# 1_P2_schdoc.net
KiCad netlist of a schematic drawn in Altium Designer
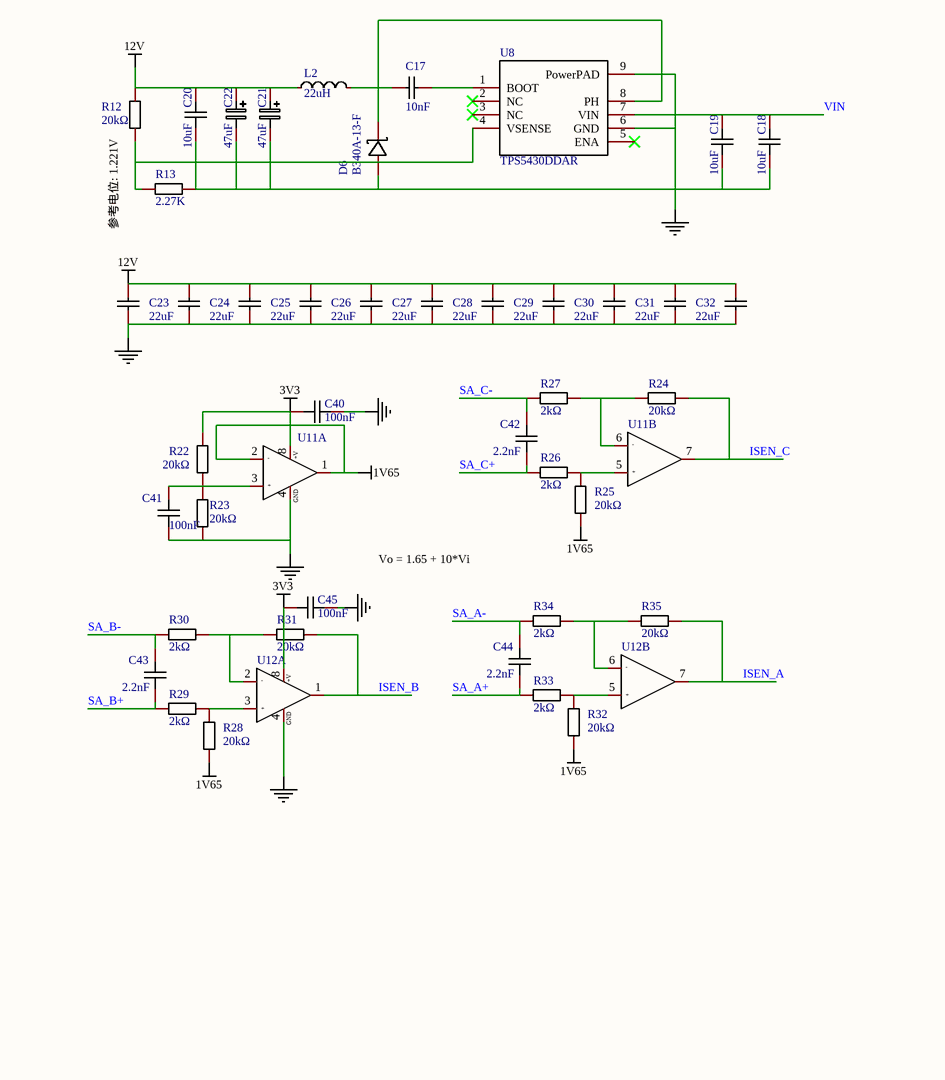
[diagram p0: 1_P2.schdoc.schdoc]

(export (version "E")
  (design (tool "Eeschema 10.0.6"))
  (components
    (comp (ref "C17")
      (value "10nF")
      (fields
        (field (name "NAME") "10nF")
        (field (name "MANUFACTURER") "YAGEO(国巨)")
        (field (name "MANUFACTURER PART") "CC0603KRX7R9BB103")
        (field (name "TOLERANCE") "±10%")
      )
      (libsource (lib "altium-import") (part "root_0_CC0603KRX7R9BB103_"))
    )
    (comp (ref "C18")
      (value "10uF")
      (fields
        (field (name "NAME") "10uF")
        (field (name "MANUFACTURER") "muRata(村田)")
        (field (name "MANUFACTURER PART") "GRM21BR61H106KE43L")
        (field (name "TOLERANCE") "±10%")
      )
      (libsource (lib "altium-import") (part "root_1_GRM21BR61H106KE43L_"))
    )
    (comp (ref "C19")
      (value "10uF")
      (fields
        (field (name "NAME") "10uF")
        (field (name "MANUFACTURER") "muRata(村田)")
        (field (name "MANUFACTURER PART") "GRM21BR61H106KE43L")
        (field (name "TOLERANCE") "±10%")
      )
      (libsource (lib "altium-import") (part "root_1_GRM21BR61H106KE43L_"))
    )
    (comp (ref "C20")
      (value "10uF")
      (fields
        (field (name "NAME") "10uF")
        (field (name "MANUFACTURER") "muRata(村田)")
        (field (name "MANUFACTURER PART") "GRM21BR61H106KE43L")
        (field (name "TOLERANCE") "±10%")
      )
      (libsource (lib "altium-import") (part "root_1_GRM21BR61H106KE43L_"))
    )
    (comp (ref "C21")
      (value "47uF")
      (fields
        (field (name "NAME") "47uF")
        (field (name "MANUFACTURER") "CEC(振华新云)")
        (field (name "MANUFACTURER PART") "CA45-B-16V-47uF-K")
        (field (name "TOLERANCE") "±10%")
      )
      (libsource (lib "altium-import") (part "root_1_CA45-B-16V-47uF-K_"))
    )
    (comp (ref "C22")
      (value "47uF")
      (fields
        (field (name "NAME") "47uF")
        (field (name "MANUFACTURER") "CEC(振华新云)")
        (field (name "MANUFACTURER PART") "CA45-B-16V-47uF-K")
        (field (name "TOLERANCE") "±10%")
      )
      (libsource (lib "altium-import") (part "root_1_CA45-B-16V-47uF-K_"))
    )
    (comp (ref "C23")
      (value "22uF")
      (fields
        (field (name "NAME") "22uF")
        (field (name "MANUFACTURER PART") "CL31A226KAHNNNE")
        (field (name "MANUFACTURER") "SAMSUNG(三星)")
        (field (name "TOLERANCE") "±10%")
      )
      (libsource (lib "altium-import") (part "root_1_CL31A226KAHNNNE_"))
    )
    (comp (ref "C24")
      (value "22uF")
      (fields
        (field (name "NAME") "22uF")
        (field (name "MANUFACTURER PART") "CL31A226KAHNNNE")
        (field (name "MANUFACTURER") "SAMSUNG(三星)")
        (field (name "TOLERANCE") "±10%")
      )
      (libsource (lib "altium-import") (part "root_1_CL31A226KAHNNNE_"))
    )
    (comp (ref "C25")
      (value "22uF")
      (fields
        (field (name "NAME") "22uF")
        (field (name "MANUFACTURER PART") "CL31A226KAHNNNE")
        (field (name "MANUFACTURER") "SAMSUNG(三星)")
        (field (name "TOLERANCE") "±10%")
      )
      (libsource (lib "altium-import") (part "root_1_CL31A226KAHNNNE_"))
    )
    (comp (ref "C26")
      (value "22uF")
      (fields
        (field (name "NAME") "22uF")
        (field (name "MANUFACTURER PART") "CL31A226KAHNNNE")
        (field (name "MANUFACTURER") "SAMSUNG(三星)")
        (field (name "TOLERANCE") "±10%")
      )
      (libsource (lib "altium-import") (part "root_1_CL31A226KAHNNNE_"))
    )
    (comp (ref "C27")
      (value "22uF")
      (fields
        (field (name "NAME") "22uF")
        (field (name "MANUFACTURER PART") "CL31A226KAHNNNE")
        (field (name "MANUFACTURER") "SAMSUNG(三星)")
        (field (name "TOLERANCE") "±10%")
      )
      (libsource (lib "altium-import") (part "root_1_CL31A226KAHNNNE_"))
    )
    (comp (ref "C28")
      (value "22uF")
      (fields
        (field (name "NAME") "22uF")
        (field (name "MANUFACTURER PART") "CL31A226KAHNNNE")
        (field (name "MANUFACTURER") "SAMSUNG(三星)")
        (field (name "TOLERANCE") "±10%")
      )
      (libsource (lib "altium-import") (part "root_1_CL31A226KAHNNNE_"))
    )
    (comp (ref "C29")
      (value "22uF")
      (fields
        (field (name "NAME") "22uF")
        (field (name "MANUFACTURER PART") "CL31A226KAHNNNE")
        (field (name "MANUFACTURER") "SAMSUNG(三星)")
        (field (name "TOLERANCE") "±10%")
      )
      (libsource (lib "altium-import") (part "root_1_CL31A226KAHNNNE_"))
    )
    (comp (ref "C30")
      (value "22uF")
      (fields
        (field (name "NAME") "22uF")
        (field (name "MANUFACTURER PART") "CL31A226KAHNNNE")
        (field (name "MANUFACTURER") "SAMSUNG(三星)")
        (field (name "TOLERANCE") "±10%")
      )
      (libsource (lib "altium-import") (part "root_1_CL31A226KAHNNNE_"))
    )
    (comp (ref "C31")
      (value "22uF")
      (fields
        (field (name "NAME") "22uF")
        (field (name "MANUFACTURER PART") "CL31A226KAHNNNE")
        (field (name "MANUFACTURER") "SAMSUNG(三星)")
        (field (name "TOLERANCE") "±10%")
      )
      (libsource (lib "altium-import") (part "root_1_CL31A226KAHNNNE_"))
    )
    (comp (ref "C32")
      (value "22uF")
      (fields
        (field (name "NAME") "22uF")
        (field (name "MANUFACTURER PART") "CL31A226KAHNNNE")
        (field (name "MANUFACTURER") "SAMSUNG(三星)")
        (field (name "TOLERANCE") "±10%")
      )
      (libsource (lib "altium-import") (part "root_1_CL31A226KAHNNNE_"))
    )
    (comp (ref "C33")
      (value "22uF")
      (fields
        (field (name "MANUFACTURER PART") "CL31A226KAHNNNE")
        (field (name "MANUFACTURER") "SAMSUNG(三星)")
        (field (name "TOLERANCE") "±10%")
      )
      (libsource (lib "altium-import") (part "root_1_CL31A226KAHNNNE_"))
    )
    (comp (ref "C40")
      (value "100nF")
      (fields
        (field (name "NAME") "100nF")
        (field (name "MANUFACTURER") "FH(风华)")
        (field (name "MANUFACTURER PART") "0603B104K500NT")
        (field (name "TOLERANCE") "±10%")
      )
      (libsource (lib "altium-import") (part "root_0_0603B104K500NT_"))
    )
    (comp (ref "C41")
      (value "100nF")
      (fields
        (field (name "NAME") "100nF")
        (field (name "MANUFACTURER") "FH(风华)")
        (field (name "MANUFACTURER PART") "0603B104K500NT")
        (field (name "TOLERANCE") "±10%")
      )
      (libsource (lib "altium-import") (part "root_1_0603B104K500NT_"))
    )
    (comp (ref "C42")
      (value "2.2nF")
      (fields
        (field (name "NAME") "2.2nF")
        (field (name "MANUFACTURER") "FH(风华)")
        (field (name "MANUFACTURER PART") "0603B222K500NT")
        (field (name "TOLERANCE") "±10%")
      )
      (libsource (lib "altium-import") (part "root_1_0603B222K500NT_"))
    )
    (comp (ref "C43")
      (value "2.2nF")
      (fields
        (field (name "NAME") "2.2nF")
        (field (name "MANUFACTURER") "FH(风华)")
        (field (name "MANUFACTURER PART") "0603B222K500NT")
        (field (name "TOLERANCE") "±10%")
      )
      (libsource (lib "altium-import") (part "root_1_0603B222K500NT_"))
    )
    (comp (ref "C44")
      (value "2.2nF")
      (fields
        (field (name "NAME") "2.2nF")
        (field (name "MANUFACTURER") "FH(风华)")
        (field (name "MANUFACTURER PART") "0603B222K500NT")
        (field (name "TOLERANCE") "±10%")
      )
      (libsource (lib "altium-import") (part "root_1_0603B222K500NT_"))
    )
    (comp (ref "C45")
      (value "100nF")
      (fields
        (field (name "NAME") "100nF")
        (field (name "MANUFACTURER") "FH(风华)")
        (field (name "MANUFACTURER PART") "0603B104K500NT")
        (field (name "TOLERANCE") "±10%")
      )
      (libsource (lib "altium-import") (part "root_0_0603B104K500NT_"))
    )
    (comp (ref "D6")
      (value "B340A-13-F")
      (description "正向压降(Vf):500mV@3A;直流反向耐压(Vr):40V;平均整流电流(Io):3A;")
      (fields (field (name "NAME") "B340A-13-F") (field (name "MANUFACTURER") "DIODES(美台)"))
      (libsource (lib "altium-import") (part "root_3_B340A-13-F_"))
    )
    (comp (ref "L2")
      (value "22uH")
      (fields
        (field (name "NAME") "22uH")
        (field (name "MANUFACTURER") "cjiang(长江微电)")
        (field (name "MANUFACTURER PART") "FXL0630-220-M")
        (field (name "TOLERANCE") "±20%")
      )
      (libsource (lib "altium-import") (part "root_0_FXL0630-220-M_"))
    )
    (comp (ref "R12")
      (value "20kΩ")
      (fields
        (field (name "NAME") "20kΩ")
        (field (name "MANUFACTURER") "UNI-ROYAL(厚声)")
        (field (name "MANUFACTURER PART") "0603WAF2002T5E")
        (field (name "TOLERANCE") "±1%")
      )
      (libsource (lib "altium-import") (part "root_1_0603WAF2002T5E_"))
    )
    (comp (ref "R13")
      (value "2.27K")
      (fields (field (name "NAME") "2.27K"))
      (libsource (lib "altium-import") (part "root_2_Res_0603_"))
    )
    (comp (ref "R22")
      (value "20kΩ")
      (fields
        (field (name "NAME") "20kΩ")
        (field (name "MANUFACTURER") "UNI-ROYAL(厚声)")
        (field (name "MANUFACTURER PART") "0603WAF2002T5E")
        (field (name "TOLERANCE") "±1%")
      )
      (libsource (lib "altium-import") (part "root_1_0603WAF2002T5E_"))
    )
    (comp (ref "R23")
      (value "20kΩ")
      (fields
        (field (name "NAME") "20kΩ")
        (field (name "MANUFACTURER") "UNI-ROYAL(厚声)")
        (field (name "MANUFACTURER PART") "0603WAF2002T5E")
        (field (name "TOLERANCE") "±1%")
      )
      (libsource (lib "altium-import") (part "root_1_0603WAF2002T5E_"))
    )
    (comp (ref "R24")
      (value "20kΩ")
      (fields
        (field (name "NAME") "20kΩ")
        (field (name "MANUFACTURER") "UNI-ROYAL(厚声)")
        (field (name "MANUFACTURER PART") "0603WAF2002T5E")
        (field (name "TOLERANCE") "±1%")
      )
      (libsource (lib "altium-import") (part "root_0_0603WAF2002T5E_"))
    )
    (comp (ref "R25")
      (value "20kΩ")
      (fields
        (field (name "NAME") "20kΩ")
        (field (name "MANUFACTURER") "UNI-ROYAL(厚声)")
        (field (name "MANUFACTURER PART") "0603WAF2002T5E")
        (field (name "TOLERANCE") "±1%")
      )
      (libsource (lib "altium-import") (part "root_1_0603WAF2002T5E_"))
    )
    (comp (ref "R26")
      (value "2kΩ")
      (fields
        (field (name "NAME") "2kΩ")
        (field (name "MANUFACTURER") "UNI-ROYAL(厚声)")
        (field (name "MANUFACTURER PART") "0603WAF2001T5E")
        (field (name "TOLERANCE") "±1%")
      )
      (libsource (lib "altium-import") (part "root_0_0603WAF2001T5E_"))
    )
    (comp (ref "R27")
      (value "2kΩ")
      (fields
        (field (name "NAME") "2kΩ")
        (field (name "MANUFACTURER") "UNI-ROYAL(厚声)")
        (field (name "MANUFACTURER PART") "0603WAF2001T5E")
        (field (name "TOLERANCE") "±1%")
      )
      (libsource (lib "altium-import") (part "root_0_0603WAF2001T5E_"))
    )
    (comp (ref "R28")
      (value "20kΩ")
      (fields
        (field (name "NAME") "20kΩ")
        (field (name "MANUFACTURER") "UNI-ROYAL(厚声)")
        (field (name "MANUFACTURER PART") "0603WAF2002T5E")
        (field (name "TOLERANCE") "±1%")
      )
      (libsource (lib "altium-import") (part "root_1_0603WAF2002T5E_"))
    )
    (comp (ref "R29")
      (value "2kΩ")
      (fields
        (field (name "NAME") "2kΩ")
        (field (name "MANUFACTURER") "UNI-ROYAL(厚声)")
        (field (name "MANUFACTURER PART") "0603WAF2001T5E")
        (field (name "TOLERANCE") "±1%")
      )
      (libsource (lib "altium-import") (part "root_0_0603WAF2001T5E_"))
    )
    (comp (ref "R30")
      (value "2kΩ")
      (fields
        (field (name "NAME") "2kΩ")
        (field (name "MANUFACTURER") "UNI-ROYAL(厚声)")
        (field (name "MANUFACTURER PART") "0603WAF2001T5E")
        (field (name "TOLERANCE") "±1%")
      )
      (libsource (lib "altium-import") (part "root_0_0603WAF2001T5E_"))
    )
    (comp (ref "R31")
      (value "20kΩ")
      (fields
        (field (name "NAME") "20kΩ")
        (field (name "MANUFACTURER") "UNI-ROYAL(厚声)")
        (field (name "MANUFACTURER PART") "0603WAF2002T5E")
        (field (name "TOLERANCE") "±1%")
      )
      (libsource (lib "altium-import") (part "root_0_0603WAF2002T5E_"))
    )
    (comp (ref "R32")
      (value "20kΩ")
      (fields
        (field (name "NAME") "20kΩ")
        (field (name "MANUFACTURER") "UNI-ROYAL(厚声)")
        (field (name "MANUFACTURER PART") "0603WAF2002T5E")
        (field (name "TOLERANCE") "±1%")
      )
      (libsource (lib "altium-import") (part "root_1_0603WAF2002T5E_"))
    )
    (comp (ref "R33")
      (value "2kΩ")
      (fields
        (field (name "NAME") "2kΩ")
        (field (name "MANUFACTURER") "UNI-ROYAL(厚声)")
        (field (name "MANUFACTURER PART") "0603WAF2001T5E")
        (field (name "TOLERANCE") "±1%")
      )
      (libsource (lib "altium-import") (part "root_0_0603WAF2001T5E_"))
    )
    (comp (ref "R34")
      (value "2kΩ")
      (fields
        (field (name "NAME") "2kΩ")
        (field (name "MANUFACTURER") "UNI-ROYAL(厚声)")
        (field (name "MANUFACTURER PART") "0603WAF2001T5E")
        (field (name "TOLERANCE") "±1%")
      )
      (libsource (lib "altium-import") (part "root_0_0603WAF2001T5E_"))
    )
    (comp (ref "R35")
      (value "20kΩ")
      (fields
        (field (name "NAME") "20kΩ")
        (field (name "MANUFACTURER") "UNI-ROYAL(厚声)")
        (field (name "MANUFACTURER PART") "0603WAF2002T5E")
        (field (name "TOLERANCE") "±1%")
      )
      (libsource (lib "altium-import") (part "root_0_0603WAF2002T5E_"))
    )
    (comp (ref "U8")
      (value "TPS5430DDAR")
      (description "功能类型:降压型;输出类型:可调;输入电压:5.5V~36V;输出电压:1.221V~32.04V;输出电流(最大值):3A;")
      (fields (field (name "NAME") "TPS5430DDAR") (field (name "MANUFACTURER") "TI(德州仪器)"))
      (libsource (lib "altium-import") (part "root_0_TPS5430DDAR_"))
    )
    (comp (ref "U11")
      (value "LM358DR")
      (description "放大器数:双路;增益带宽积(GBP):700kHz;输入偏置电流(Ib):20nA;压摆率(SR):0.3V/us;带宽(-3db):-;")
      (fields (field (name "MANUFACTURER") "TI(德州仪器)"))
      (libsource (lib "altium-import") (part "root_0_LM358DR_"))
    )
    (comp (ref "U12")
      (value "LM358DR")
      (description "放大器数:双路;增益带宽积(GBP):700kHz;输入偏置电流(Ib):20nA;压摆率(SR):0.3V/us;带宽(-3db):-;")
      (fields (field (name "MANUFACTURER") "TI(德州仪器)"))
      (libsource (lib "altium-import") (part "root_0_LM358DR_"))
    )
  )
  (nets
    (net (code "1") (name "/ISEN_A") (class "Default")
      (node (ref "R35") (pin "2") (pinfunction "2_2") (pintype "passive"))
      (node (ref "U12") (pin "7") (pinfunction "OUT2_7") (pintype "passive"))
    )
    (net (code "2") (name "/ISEN_B") (class "Default")
      (node (ref "R31") (pin "2") (pinfunction "2_2") (pintype "passive"))
      (node (ref "U12") (pin "1") (pinfunction "OUT1_1") (pintype "passive"))
    )
    (net (code "3") (name "/ISEN_C") (class "Default")
      (node (ref "R24") (pin "2") (pinfunction "2_2") (pintype "passive"))
      (node (ref "U11") (pin "7") (pinfunction "OUT2_7") (pintype "passive"))
    )
    (net (code "4") (name "/SA_A+") (class "Default")
      (node (ref "C44") (pin "1") (pinfunction "1_1") (pintype "passive"))
      (node (ref "R33") (pin "1") (pinfunction "1_1") (pintype "passive"))
    )
    (net (code "5") (name "/SA_A-") (class "Default")
      (node (ref "C44") (pin "2") (pinfunction "2_2") (pintype "passive"))
      (node (ref "R34") (pin "1") (pinfunction "1_1") (pintype "passive"))
    )
    (net (code "6") (name "/SA_B+") (class "Default")
      (node (ref "C43") (pin "1") (pinfunction "1_1") (pintype "passive"))
      (node (ref "R29") (pin "1") (pinfunction "1_1") (pintype "passive"))
    )
    (net (code "7") (name "/SA_B-") (class "Default")
      (node (ref "C43") (pin "2") (pinfunction "2_2") (pintype "passive"))
      (node (ref "R30") (pin "1") (pinfunction "1_1") (pintype "passive"))
    )
    (net (code "8") (name "/SA_C+") (class "Default")
      (node (ref "C42") (pin "1") (pinfunction "1_1") (pintype "passive"))
      (node (ref "R26") (pin "1") (pinfunction "1_1") (pintype "passive"))
    )
    (net (code "9") (name "/SA_C-") (class "Default")
      (node (ref "C42") (pin "2") (pinfunction "2_2") (pintype "passive"))
      (node (ref "R27") (pin "1") (pinfunction "1_1") (pintype "passive"))
    )
    (net (code "10") (name "/VIN") (class "Default")
      (node (ref "C18") (pin "2") (pinfunction "2_2") (pintype "passive"))
      (node (ref "C19") (pin "2") (pinfunction "2_2") (pintype "passive"))
      (node (ref "U8") (pin "7") (pinfunction "VIN_7") (pintype "passive"))
    )
    (net (code "11") (name "1V65") (class "Default")
      (node (ref "R25") (pin "1") (pinfunction "1_1") (pintype "passive"))
      (node (ref "R28") (pin "1") (pinfunction "1_1") (pintype "passive"))
      (node (ref "R32") (pin "1") (pinfunction "1_1") (pintype "passive"))
      (node (ref "U11") (pin "1") (pinfunction "OUT1_1") (pintype "passive"))
      (node (ref "U11") (pin "2") (pinfunction "-IN1_2") (pintype "passive"))
    )
    (net (code "12") (name "3V3") (class "Default")
      (node (ref "C40") (pin "1") (pinfunction "1_1") (pintype "passive"))
      (node (ref "C45") (pin "1") (pinfunction "1_1") (pintype "passive"))
      (node (ref "R22") (pin "2") (pinfunction "2_2") (pintype "passive"))
      (node (ref "U11") (pin "8") (pinfunction "+V_8") (pintype "passive"))
      (node (ref "U12") (pin "8") (pinfunction "+V_8") (pintype "passive"))
    )
    (net (code "13") (name "12V") (class "Default")
      (node (ref "C20") (pin "2") (pinfunction "2_2") (pintype "passive"))
      (node (ref "C21") (pin "1") (pinfunction "1_1") (pintype "passive"))
      (node (ref "C22") (pin "1") (pinfunction "1_1") (pintype "passive"))
      (node (ref "C23") (pin "2") (pinfunction "2_2") (pintype "passive"))
      (node (ref "C24") (pin "2") (pinfunction "2_2") (pintype "passive"))
      (node (ref "C25") (pin "2") (pinfunction "2_2") (pintype "passive"))
      (node (ref "C26") (pin "2") (pinfunction "2_2") (pintype "passive"))
      (node (ref "C27") (pin "2") (pinfunction "2_2") (pintype "passive"))
      (node (ref "C28") (pin "2") (pinfunction "2_2") (pintype "passive"))
      (node (ref "C29") (pin "2") (pinfunction "2_2") (pintype "passive"))
      (node (ref "C30") (pin "2") (pinfunction "2_2") (pintype "passive"))
      (node (ref "C31") (pin "2") (pinfunction "2_2") (pintype "passive"))
      (node (ref "C32") (pin "2") (pinfunction "2_2") (pintype "passive"))
      (node (ref "C33") (pin "2") (pinfunction "2_2") (pintype "passive"))
      (node (ref "L2") (pin "1") (pinfunction "1_1") (pintype "passive"))
      (node (ref "R12") (pin "2") (pinfunction "2_2") (pintype "passive"))
    )
    (net (code "14") (name "GND") (class "Default")
      (node (ref "C18") (pin "1") (pinfunction "1_1") (pintype "passive"))
      (node (ref "C19") (pin "1") (pinfunction "1_1") (pintype "passive"))
      (node (ref "C20") (pin "1") (pinfunction "1_1") (pintype "passive"))
      (node (ref "C21") (pin "2") (pinfunction "2_2") (pintype "passive"))
      (node (ref "C22") (pin "2") (pinfunction "2_2") (pintype "passive"))
      (node (ref "C23") (pin "1") (pinfunction "1_1") (pintype "passive"))
      (node (ref "C24") (pin "1") (pinfunction "1_1") (pintype "passive"))
      (node (ref "C25") (pin "1") (pinfunction "1_1") (pintype "passive"))
      (node (ref "C26") (pin "1") (pinfunction "1_1") (pintype "passive"))
      (node (ref "C27") (pin "1") (pinfunction "1_1") (pintype "passive"))
      (node (ref "C28") (pin "1") (pinfunction "1_1") (pintype "passive"))
      (node (ref "C29") (pin "1") (pinfunction "1_1") (pintype "passive"))
      (node (ref "C30") (pin "1") (pinfunction "1_1") (pintype "passive"))
      (node (ref "C31") (pin "1") (pinfunction "1_1") (pintype "passive"))
      (node (ref "C32") (pin "1") (pinfunction "1_1") (pintype "passive"))
      (node (ref "C33") (pin "1") (pinfunction "1_1") (pintype "passive"))
      (node (ref "C40") (pin "2") (pinfunction "2_2") (pintype "passive"))
      (node (ref "C41") (pin "1") (pinfunction "1_1") (pintype "passive"))
      (node (ref "C45") (pin "2") (pinfunction "2_2") (pintype "passive"))
      (node (ref "D6") (pin "2") (pinfunction "A_2") (pintype "passive"))
      (node (ref "R13") (pin "1") (pinfunction "1_1") (pintype "passive"))
      (node (ref "R23") (pin "1") (pinfunction "1_1") (pintype "passive"))
      (node (ref "U11") (pin "4") (pinfunction "GND_4") (pintype "passive"))
      (node (ref "U12") (pin "4") (pinfunction "GND_4") (pintype "passive"))
      (node (ref "U8") (pin "6") (pinfunction "GND_6") (pintype "passive"))
      (node (ref "U8") (pin "9") (pinfunction "PowerPAD_9") (pintype "passive"))
    )
    (net (code "15") (name "Net-(D6-K)") (class "Default")
      (node (ref "C17") (pin "1") (pinfunction "1_1") (pintype "passive"))
      (node (ref "D6") (pin "1") (pinfunction "K_1") (pintype "passive"))
      (node (ref "L2") (pin "2") (pinfunction "2_2") (pintype "passive"))
      (node (ref "U8") (pin "8") (pinfunction "PH_8") (pintype "passive"))
    )
    (net (code "16") (name "Net-(U8-BOOT)") (class "Default")
      (node (ref "C17") (pin "2") (pinfunction "2_2") (pintype "passive"))
      (node (ref "U8") (pin "1") (pinfunction "BOOT_1") (pintype "passive"))
    )
    (net (code "17") (name "Net-(U8-VSENSE)") (class "Default")
      (node (ref "R12") (pin "1") (pinfunction "1_1") (pintype "passive"))
      (node (ref "R13") (pin "2") (pinfunction "2_2") (pintype "passive"))
      (node (ref "U8") (pin "4") (pinfunction "VSENSE_4") (pintype "passive"))
    )
    (net (code "18") (name "Net-(U11A-+IN1)") (class "Default")
      (node (ref "C41") (pin "2") (pinfunction "2_2") (pintype "passive"))
      (node (ref "R22") (pin "1") (pinfunction "1_1") (pintype "passive"))
      (node (ref "R23") (pin "2") (pinfunction "2_2") (pintype "passive"))
      (node (ref "U11") (pin "3") (pinfunction "+IN1_3") (pintype "passive"))
    )
    (net (code "19") (name "Net-(U11B-+IN2)") (class "Default")
      (node (ref "R25") (pin "2") (pinfunction "2_2") (pintype "passive"))
      (node (ref "R26") (pin "2") (pinfunction "2_2") (pintype "passive"))
      (node (ref "U11") (pin "5") (pinfunction "+IN2_5") (pintype "passive"))
    )
    (net (code "20") (name "Net-(U11B--IN2)") (class "Default")
      (node (ref "R24") (pin "1") (pinfunction "1_1") (pintype "passive"))
      (node (ref "R27") (pin "2") (pinfunction "2_2") (pintype "passive"))
      (node (ref "U11") (pin "6") (pinfunction "-IN2_6") (pintype "passive"))
    )
    (net (code "21") (name "Net-(U12A-+IN1)") (class "Default")
      (node (ref "R28") (pin "2") (pinfunction "2_2") (pintype "passive"))
      (node (ref "R29") (pin "2") (pinfunction "2_2") (pintype "passive"))
      (node (ref "U12") (pin "3") (pinfunction "+IN1_3") (pintype "passive"))
    )
    (net (code "22") (name "Net-(U12A--IN1)") (class "Default")
      (node (ref "R30") (pin "2") (pinfunction "2_2") (pintype "passive"))
      (node (ref "R31") (pin "1") (pinfunction "1_1") (pintype "passive"))
      (node (ref "U12") (pin "2") (pinfunction "-IN1_2") (pintype "passive"))
    )
    (net (code "23") (name "Net-(U12B-+IN2)") (class "Default")
      (node (ref "R32") (pin "2") (pinfunction "2_2") (pintype "passive"))
      (node (ref "R33") (pin "2") (pinfunction "2_2") (pintype "passive"))
      (node (ref "U12") (pin "5") (pinfunction "+IN2_5") (pintype "passive"))
    )
    (net (code "24") (name "Net-(U12B--IN2)") (class "Default")
      (node (ref "R34") (pin "2") (pinfunction "2_2") (pintype "passive"))
      (node (ref "R35") (pin "1") (pinfunction "1_1") (pintype "passive"))
      (node (ref "U12") (pin "6") (pinfunction "-IN2_6") (pintype "passive"))
    )
    (net (code "25") (name "unconnected-(U8-ENA-Pad5)") (class "Default")
      (node (ref "U8") (pin "5") (pinfunction "ENA_5") (pintype "passive+no_connect"))
    )
    (net (code "26") (name "unconnected-(U8-NC-Pad2)") (class "Default")
      (node (ref "U8") (pin "2") (pinfunction "NC_2") (pintype "passive+no_connect"))
    )
    (net (code "27") (name "unconnected-(U8-NC-Pad3)") (class "Default")
      (node (ref "U8") (pin "3") (pinfunction "NC_3") (pintype "passive+no_connect"))
    )
  )
)
